# LEDProbe.net
KiCad netlist of a schematic drawn in EAGLE
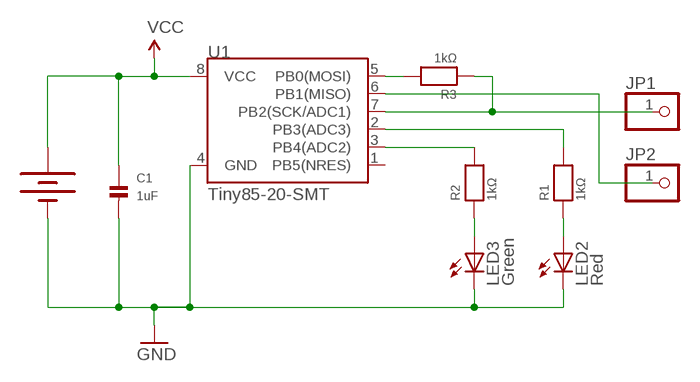
[diagram p0: schematic, sheet 1]

(export (version "E")
  (design (tool "Eeschema 10.0.6"))
  (components
    (comp (ref "BAT2")
      (value "20mm coincell")
      (footprint "eagle-import:BATTCON_20MM_4LEGS")
      (libsource (lib "eagle-import") (part "BATTERY20MM_4LEGS"))
    )
    (comp (ref "C1")
      (value "1uF")
      (footprint "eagle-import:_0805MP")
      (libsource (lib "eagle-import") (part "CAP_CERAMIC_0805MP"))
    )
    (comp (ref "JP1")
      (value "PINHD-1X1CB")
      (footprint "eagle-import:1X01-CLEANBIG")
      (libsource (lib "eagle-import") (part "PINHD-1X1CB"))
    )
    (comp (ref "JP2")
      (value "PINHD-1X1CB")
      (footprint "eagle-import:1X01-CLEANBIG")
      (libsource (lib "eagle-import") (part "PINHD-1X1CB"))
    )
    (comp (ref "LED2")
      (value "Red")
      (footprint "eagle-import:CHIPLED_0805")
      (libsource (lib "eagle-import") (part "LEDCHIPLED_0805"))
    )
    (comp (ref "LED3")
      (value "Green")
      (footprint "eagle-import:CHIPLED_0805")
      (libsource (lib "eagle-import") (part "LEDCHIPLED_0805"))
    )
    (comp (ref "R1")
      (value "1kΩ")
      (footprint "eagle-import:_0805MP")
      (libsource (lib "eagle-import") (part "RESISTOR_0805MP"))
    )
    (comp (ref "R2")
      (value "1kΩ")
      (footprint "eagle-import:_0805MP")
      (libsource (lib "eagle-import") (part "RESISTOR_0805MP"))
    )
    (comp (ref "R3")
      (value "1kΩ")
      (footprint "eagle-import:_0805MP")
      (libsource (lib "eagle-import") (part "RESISTOR_0805MP"))
    )
    (comp (ref "U1")
      (value "Tiny85-20-SMT")
      (footprint "eagle-import:SO08-EIAJ")
      (libsource (lib "eagle-import") (part "ATTINY45TINY85-20-SMT"))
    )
  )
  (nets
    (net (code "1") (name "GND") (class "Default")
      (node (ref "BAT2") (pin "NEGATIVE") (pinfunction "-_NEGATIVE") (pintype "power_in"))
      (node (ref "C1") (pin "2") (pinfunction "P$2_2") (pintype "passive"))
      (node (ref "LED2") (pin "C") (pinfunction "C_C") (pintype "passive"))
      (node (ref "LED3") (pin "C") (pinfunction "C_C") (pintype "passive"))
      (node (ref "U1") (pin "4") (pinfunction "GND_4") (pintype "bidirectional"))
    )
    (net (code "2") (name "Net-(LED2-PadA)") (class "Default")
      (node (ref "LED2") (pin "A") (pinfunction "A_A") (pintype "passive"))
      (node (ref "R1") (pin "1") (pinfunction "1_1") (pintype "passive"))
    )
    (net (code "3") (name "Net-(LED3-PadA)") (class "Default")
      (node (ref "LED3") (pin "A") (pinfunction "A_A") (pintype "passive"))
      (node (ref "R2") (pin "1") (pinfunction "1_1") (pintype "passive"))
    )
    (net (code "4") (name "Net-(U1-PB0(MOSI))") (class "Default")
      (node (ref "R3") (pin "2") (pinfunction "2_2") (pintype "passive"))
      (node (ref "U1") (pin "5") (pinfunction "PB0(MOSI)_5") (pintype "bidirectional"))
    )
    (net (code "5") (name "Net-(U1-PB1(MISO))") (class "Default")
      (node (ref "JP2") (pin "1") (pinfunction "1_1") (pintype "passive"))
      (node (ref "U1") (pin "6") (pinfunction "PB1(MISO)_6") (pintype "bidirectional"))
    )
    (net (code "6") (name "Net-(U1-PB2(SCK{slash}ADC1))") (class "Default")
      (node (ref "JP1") (pin "1") (pinfunction "1_1") (pintype "passive"))
      (node (ref "R3") (pin "1") (pinfunction "1_1") (pintype "passive"))
      (node (ref "U1") (pin "7") (pinfunction "PB2(SCK/ADC1)_7") (pintype "bidirectional"))
    )
    (net (code "7") (name "Net-(U1-PB3(ADC3))") (class "Default")
      (node (ref "R1") (pin "2") (pinfunction "2_2") (pintype "passive"))
      (node (ref "U1") (pin "2") (pinfunction "PB3(ADC3)_2") (pintype "bidirectional"))
    )
    (net (code "8") (name "Net-(U1-PB4(ADC2))") (class "Default")
      (node (ref "R2") (pin "2") (pinfunction "2_2") (pintype "passive"))
      (node (ref "U1") (pin "3") (pinfunction "PB4(ADC2)_3") (pintype "bidirectional"))
    )
    (net (code "9") (name "VCC") (class "Default")
      (node (ref "BAT2") (pin "POSITIVE@1") (pinfunction "+_POSITIVE@1") (pintype "power_in"))
      (node (ref "BAT2") (pin "POSITIVE@2") (pinfunction "+_POSITIVE@2") (pintype "power_in"))
      (node (ref "BAT2") (pin "POSITIVE@3") (pinfunction "+_POSITIVE@3") (pintype "power_in"))
      (node (ref "BAT2") (pin "POSITIVE@4") (pinfunction "+_POSITIVE@4") (pintype "power_in"))
      (node (ref "C1") (pin "1") (pinfunction "P$1_1") (pintype "passive"))
      (node (ref "U1") (pin "8") (pinfunction "VCC_8") (pintype "bidirectional"))
    )
    (net (code "10") (name "unconnected-(U1-PB5(NRES)-Pad1)") (class "Default")
      (node (ref "U1") (pin "1") (pinfunction "PB5(NRES)_1") (pintype "bidirectional"))
    )
  )
)
